# mcu_gateway.net
KiCad netlist of a schematic drawn in Altium Designer
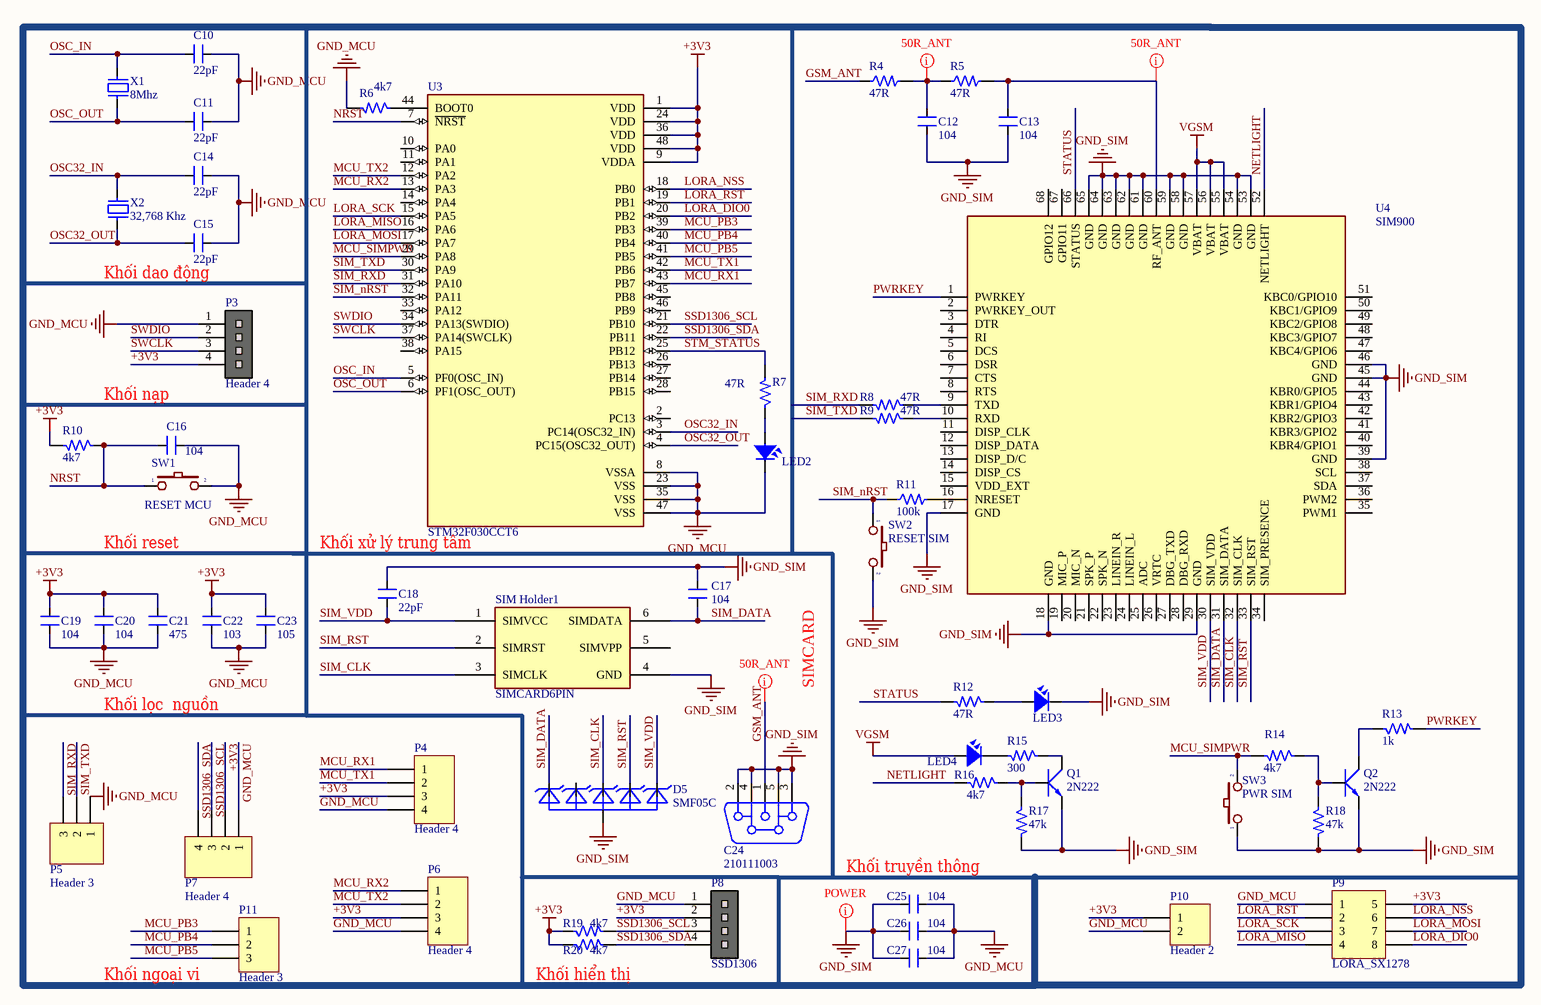
[diagram p0: mcu_gateway.SchDoc]

(export (version "E")
  (design (tool "Eeschema 10.0.6"))
  (components
    (comp (ref "C10")
      (value "22pF")
      (footprint "SM-0805")
      (description "Cap SMD")
      (libsource (lib "syhaunguyen") (part "CM"))
    )
    (comp (ref "C11")
      (value "22pF")
      (footprint "SM-0805")
      (description "Cap SMD")
      (libsource (lib "syhaunguyen") (part "CM"))
    )
    (comp (ref "C12")
      (value "104")
      (footprint "SM-0805")
      (description "Cap SMD")
      (libsource (lib "syhaunguyen") (part "CM"))
    )
    (comp (ref "C13")
      (value "104")
      (footprint "SM-0805")
      (description "Cap SMD")
      (libsource (lib "syhaunguyen") (part "CM"))
    )
    (comp (ref "C14")
      (value "22pF")
      (footprint "SM-0805")
      (description "Cap SMD")
      (libsource (lib "syhaunguyen") (part "CM"))
    )
    (comp (ref "C15")
      (value "22pF")
      (footprint "SM-0805")
      (description "Cap SMD")
      (libsource (lib "syhaunguyen") (part "CM"))
    )
    (comp (ref "C16")
      (value "104")
      (footprint "SM-0805")
      (description "Cap SMD")
      (libsource (lib "syhaunguyen") (part "CM"))
    )
    (comp (ref "C17")
      (value "104")
      (footprint "SM-0805")
      (description "Cap SMD")
      (libsource (lib "syhaunguyen") (part "CM"))
    )
    (comp (ref "C18")
      (value "22pF")
      (footprint "SM-0805")
      (description "Cap SMD")
      (libsource (lib "syhaunguyen") (part "CM"))
    )
    (comp (ref "C19")
      (value "104")
      (footprint "SM-0805")
      (description "Cap SMD")
      (libsource (lib "syhaunguyen") (part "CM"))
    )
    (comp (ref "C20")
      (value "104")
      (footprint "SM-0805")
      (description "Cap SMD")
      (libsource (lib "syhaunguyen") (part "CM"))
    )
    (comp (ref "C21")
      (value "475")
      (footprint "SM-0805")
      (description "Cap SMD")
      (libsource (lib "syhaunguyen") (part "CM"))
    )
    (comp (ref "C22")
      (value "103")
      (footprint "SM-0805")
      (description "Cap SMD")
      (libsource (lib "syhaunguyen") (part "CM"))
    )
    (comp (ref "C23")
      (value "105")
      (footprint "SM-0805")
      (description "Cap SMD")
      (libsource (lib "syhaunguyen") (part "CM"))
    )
    (comp (ref "C24")
      (value "210111003")
      (footprint "SMA-RA")
      (description "CONNECTOR ANTEN")
      (fields
        (field (name "MANUFACTURER") "Würth Elektronik eiSos GmbH")
        (field (name "CREATED BY") "Christin Zierenner")
      )
      (libsource (lib "TechMT.VN_Lib_Project v2") (part "CON Ant"))
    )
    (comp (ref "C25")
      (value "104")
      (footprint "SM-0805")
      (description "Cap SMD")
      (libsource (lib "syhaunguyen") (part "CM"))
    )
    (comp (ref "C26")
      (value "104")
      (footprint "SM-0805")
      (description "Cap SMD")
      (libsource (lib "syhaunguyen") (part "CM"))
    )
    (comp (ref "C27")
      (value "104")
      (footprint "SM-0805")
      (description "Cap SMD")
      (libsource (lib "syhaunguyen") (part "CM"))
    )
    (comp (ref "D5")
      (value "SMF05C")
      (footprint "SC70-6")
      (description "12.5V Clamp 8A _8/20Âµs_ Ipp Tvs Diode Surface Mount SC-88/SC70-6/SOT-363")
      (fields (field (name "MF") "ON Semiconductor"))
      (libsource (lib "SMF05C") (part "SMF05C"))
    )
    (comp (ref "LED2")
      (value "LED")
      (footprint "LED-0805-Green")
      (libsource (lib "TechMT.VN_Lib_Project v2") (part "LED SMD"))
    )
    (comp (ref "LED3")
      (value "LED")
      (footprint "LED-0805-Green")
      (libsource (lib "TechMT.VN_Lib_Project v2") (part "LED SMD"))
    )
    (comp (ref "LED4")
      (value "LED")
      (footprint "LED-0805-Green")
      (libsource (lib "TechMT.VN_Lib_Project v2") (part "LED SMD"))
    )
    (comp (ref "P3")
      (value "Header 4")
      (footprint "HDR 1X4")
      (description "Header, 4-Pin")
      (libsource (lib "Ayric connectors") (part "Header 4"))
    )
    (comp (ref "P4")
      (value "Header 4")
      (footprint "HDR1X4")
      (description "Header, 4-Pin")
      (fields (field (name "PUBLISHER") "Altium Limited"))
      (libsource (lib "Library AL") (part "Header 4"))
    )
    (comp (ref "P5")
      (value "Header 3")
      (footprint "HDR1X3")
      (description "Header, 3-Pin")
      (fields (field (name "PUBLISHER") "Altium Limited"))
      (libsource (lib "") (part "Header 3_1"))
    )
    (comp (ref "P6")
      (value "Header 4")
      (footprint "HDR1X4")
      (description "Header, 4-Pin")
      (fields (field (name "PUBLISHER") "Altium Limited"))
      (libsource (lib "Library AL") (part "Header 4"))
    )
    (comp (ref "P7")
      (value "Header 4")
      (footprint "HDR1X4")
      (description "Header, 4-Pin")
      (fields (field (name "PUBLISHER") "Altium Limited"))
      (libsource (lib "") (part "Header 4_1"))
    )
    (comp (ref "P8")
      (value "SSD1306")
      (footprint "HDR 1X4")
      (description "Header, 4-Pin")
      (libsource (lib "Ayric connectors") (part "Header 4"))
    )
    (comp (ref "P9")
      (value "LORA_SX1278")
      (footprint "HDR2X4_CEN")
      (description "Header, 4-Pin, Dual row")
      (fields (field (name "PUBLISHER") "Altium Limited"))
      (libsource (lib "Library AL") (part "Header 4X2A"))
    )
    (comp (ref "P10")
      (value "Header 2")
      (footprint "HDR1X2")
      (description "Header, 2-Pin")
      (fields (field (name "PUBLISHER") "Altium Limited"))
      (libsource (lib "Library AL") (part "Header 2"))
    )
    (comp (ref "P11")
      (value "Header 3")
      (footprint "HDR1X3")
      (description "Header, 3-Pin")
      (fields (field (name "PUBLISHER") "Altium Limited"))
      (libsource (lib "Library AL") (part "Header 3"))
    )
    (comp (ref "Q1")
      (value "2N222")
      (footprint "TO92-123")
      (description "NPN 600mW, ECB")
      (fields (field (name "CREAT BY") "MT-TECH.VN"))
      (libsource (lib "TechMT.VN_Lib_Project v2") (part "2N222"))
    )
    (comp (ref "Q2")
      (value "2N222")
      (footprint "TO92-123")
      (description "NPN 600mW, ECB")
      (fields (field (name "CREAT BY") "MT-TECH.VN"))
      (libsource (lib "TechMT.VN_Lib_Project v2") (part "2N222"))
    )
    (comp (ref "R4")
      (value "47R")
      (footprint "R-0805")
      (description "dien tro")
      (libsource (lib "oggy") (part "resistor"))
    )
    (comp (ref "R5")
      (value "47R")
      (footprint "R-0805")
      (description "dien tro")
      (libsource (lib "oggy") (part "resistor"))
    )
    (comp (ref "R6")
      (value "4k7")
      (footprint "R-0805")
      (description "dien tro")
      (libsource (lib "oggy") (part "resistor"))
    )
    (comp (ref "R7")
      (value "47R")
      (footprint "R-0805")
      (description "dien tro")
      (libsource (lib "oggy") (part "resistor"))
    )
    (comp (ref "R8")
      (value "47R")
      (footprint "R-0805")
      (description "dien tro")
      (libsource (lib "oggy") (part "resistor"))
    )
    (comp (ref "R9")
      (value "47R")
      (footprint "R-0805")
      (description "dien tro")
      (libsource (lib "oggy") (part "resistor"))
    )
    (comp (ref "R10")
      (value "4k7")
      (footprint "R-0805")
      (description "dien tro")
      (libsource (lib "oggy") (part "resistor"))
    )
    (comp (ref "R11")
      (value "100k")
      (footprint "R-0805")
      (description "dien tro")
      (libsource (lib "oggy") (part "resistor"))
    )
    (comp (ref "R12")
      (value "47R")
      (footprint "R-0805")
      (description "dien tro")
      (libsource (lib "oggy") (part "resistor"))
    )
    (comp (ref "R13")
      (value "1k")
      (footprint "R-0805")
      (description "dien tro")
      (libsource (lib "oggy") (part "resistor"))
    )
    (comp (ref "R14")
      (value "4k7")
      (footprint "R-0805")
      (description "dien tro")
      (libsource (lib "oggy") (part "resistor"))
    )
    (comp (ref "R15")
      (value "300")
      (footprint "R-0805")
      (description "dien tro")
      (libsource (lib "oggy") (part "resistor"))
    )
    (comp (ref "R16")
      (value "4k7")
      (footprint "R-0805")
      (description "dien tro")
      (libsource (lib "oggy") (part "resistor"))
    )
    (comp (ref "R17")
      (value "47k")
      (footprint "R-0805")
      (description "dien tro")
      (libsource (lib "oggy") (part "resistor"))
    )
    (comp (ref "R18")
      (value "47k")
      (footprint "R-0805")
      (description "dien tro")
      (libsource (lib "oggy") (part "resistor"))
    )
    (comp (ref "R19")
      (value "4k7")
      (footprint "R-0805")
      (description "dien tro")
      (libsource (lib "oggy") (part "resistor"))
    )
    (comp (ref "R20")
      (value "4k7")
      (footprint "R-0805")
      (description "dien tro")
      (libsource (lib "oggy") (part "resistor"))
    )
    (comp (ref "SIM Holder1")
      (value "SIMCARD6PIN")
      (footprint "SIMCARD6pin")
      (libsource (lib "AYRIC Library") (part "SIMCARD6PIN"))
    )
    (comp (ref "SW1")
      (value "RESET MCU")
      (footprint "SW1-SMD")
      (description "Switch button 2 pin")
      (libsource (lib "TechMT.VN_Lib_Project v2") (part "SW2"))
    )
    (comp (ref "SW2")
      (value "RESET SIM")
      (footprint "SW1-SMD")
      (description "Switch button 2 pin")
      (libsource (lib "TechMT.VN_Lib_Project v2") (part "SW2"))
    )
    (comp (ref "SW3")
      (value "PWR SIM")
      (footprint "SW1-SMD")
      (description "Switch button 2 pin")
      (libsource (lib "TechMT.VN_Lib_Project v2") (part "SW2"))
    )
    (comp (ref "U3")
      (value "STM32F030CCT6")
      (footprint "QFP50P900X900X160-48N")
      (description "ARMÂ® CortexÂ®-M0 STM32F0 Microcontroller IC 32-Bit 48MHz 256KB _256K x 8_ FLASH 48-LQFP _7x7_")
      (fields (field (name "MF") "STMicroelectronics") (field (name "DIGI-KEY_PART_NUMBER") "497-17332-2-ND"))
      (libsource (lib "STM32F030CCT6") (part "STM32F030CCT6"))
    )
    (comp (ref "U4") (value "SIM900") (footprint "SIM900") (libsource (lib "AYRIC Library") (part "SIM900")))
    (comp (ref "X1")
      (value "8Mhz")
      (footprint "XT2")
      (description "Crystal For all Crystal 2pin.")
      (libsource (lib "syhaunguyen") (part "XT2"))
    )
    (comp (ref "X2")
      (value "32,768 Khz")
      (footprint "XT32k")
      (description "Crystal 32,768kHz for timer real")
      (libsource (lib "syhaunguyen") (part "XT32k"))
    )
  )
  (nets
    (net (code "1") (name "+3V3") (class "Default")
      (node (ref "C19") (pin "2") (pinfunction "2_2") (pintype "passive"))
      (node (ref "C20") (pin "2") (pinfunction "2_2") (pintype "passive"))
      (node (ref "C21") (pin "2") (pinfunction "2_2") (pintype "passive"))
      (node (ref "C22") (pin "2") (pinfunction "2_2") (pintype "passive"))
      (node (ref "C23") (pin "2") (pinfunction "2_2") (pintype "passive"))
      (node (ref "P10") (pin "1") (pinfunction "1_1") (pintype "passive"))
      (node (ref "P3") (pin "4") (pinfunction "4_4") (pintype "passive"))
      (node (ref "P4") (pin "3") (pinfunction "3_3") (pintype "passive"))
      (node (ref "P6") (pin "3") (pinfunction "3_3") (pintype "passive"))
      (node (ref "P7") (pin "2") (pinfunction "2_2") (pintype "passive"))
      (node (ref "P8") (pin "2") (pinfunction "2_2") (pintype "passive"))
      (node (ref "P9") (pin "5") (pinfunction "5_5") (pintype "passive"))
      (node (ref "R10") (pin "2") (pinfunction "2_2") (pintype "passive"))
      (node (ref "R19") (pin "1") (pinfunction "1_1") (pintype "passive"))
      (node (ref "R20") (pin "1") (pinfunction "1_1") (pintype "passive"))
      (node (ref "U3") (pin "1") (pinfunction "VDD_1") (pintype "power_in"))
      (node (ref "U3") (pin "24") (pinfunction "VDD_24") (pintype "power_in"))
      (node (ref "U3") (pin "36") (pinfunction "VDD_36") (pintype "power_in"))
      (node (ref "U3") (pin "48") (pinfunction "VDD_48") (pintype "power_in"))
      (node (ref "U3") (pin "9") (pinfunction "VDDA_9") (pintype "power_in"))
    )
    (net (code "2") (name "/GSM_ANT") (class "Default")
      (node (ref "C24") (pin "1") (pinfunction "1_1") (pintype "passive"))
      (node (ref "R4") (pin "1") (pinfunction "1_1") (pintype "passive"))
    )
    (net (code "3") (name "/LORA_DIO0") (class "Default")
      (node (ref "P9") (pin "8") (pinfunction "8_8") (pintype "passive"))
      (node (ref "U3") (pin "20") (pinfunction "PB2_20") (pintype "bidirectional"))
    )
    (net (code "4") (name "/LORA_MISO") (class "Default")
      (node (ref "P9") (pin "4") (pinfunction "4_4") (pintype "passive"))
      (node (ref "U3") (pin "16") (pinfunction "PA6_16") (pintype "bidirectional"))
    )
    (net (code "5") (name "/LORA_MOSI") (class "Default")
      (node (ref "P9") (pin "7") (pinfunction "7_7") (pintype "passive"))
      (node (ref "U3") (pin "17") (pinfunction "PA7_17") (pintype "bidirectional"))
    )
    (net (code "6") (name "/LORA_NSS") (class "Default")
      (node (ref "P9") (pin "6") (pinfunction "6_6") (pintype "passive"))
      (node (ref "U3") (pin "18") (pinfunction "PB0_18") (pintype "bidirectional"))
    )
    (net (code "7") (name "/LORA_RST") (class "Default")
      (node (ref "P9") (pin "2") (pinfunction "2_2") (pintype "passive"))
      (node (ref "U3") (pin "19") (pinfunction "PB1_19") (pintype "bidirectional"))
    )
    (net (code "8") (name "/LORA_SCK") (class "Default")
      (node (ref "P9") (pin "3") (pinfunction "3_3") (pintype "passive"))
      (node (ref "U3") (pin "15") (pinfunction "PA5_15") (pintype "bidirectional"))
    )
    (net (code "9") (name "/MCU_PB3") (class "Default")
      (node (ref "P11") (pin "1") (pinfunction "1_1") (pintype "passive"))
      (node (ref "U3") (pin "39") (pinfunction "PB3_39") (pintype "bidirectional"))
    )
    (net (code "10") (name "/MCU_PB4") (class "Default")
      (node (ref "P11") (pin "2") (pinfunction "2_2") (pintype "passive"))
      (node (ref "U3") (pin "40") (pinfunction "PB4_40") (pintype "bidirectional"))
    )
    (net (code "11") (name "/MCU_PB5") (class "Default")
      (node (ref "P11") (pin "3") (pinfunction "3_3") (pintype "passive"))
      (node (ref "U3") (pin "41") (pinfunction "PB5_41") (pintype "bidirectional"))
    )
    (net (code "12") (name "/MCU_RX1") (class "Default")
      (node (ref "P4") (pin "1") (pinfunction "1_1") (pintype "passive"))
      (node (ref "U3") (pin "43") (pinfunction "PB7_43") (pintype "bidirectional"))
    )
    (net (code "13") (name "/MCU_RX2") (class "Default")
      (node (ref "P6") (pin "1") (pinfunction "1_1") (pintype "passive"))
      (node (ref "U3") (pin "13") (pinfunction "PA3_13") (pintype "bidirectional"))
    )
    (net (code "14") (name "/MCU_SIMPWR") (class "Default")
      (node (ref "R14") (pin "2") (pinfunction "2_2") (pintype "passive"))
      (node (ref "SW3") (pin "2") (pinfunction "2_2") (pintype "passive"))
      (node (ref "U3") (pin "29") (pinfunction "PA8_29") (pintype "bidirectional"))
    )
    (net (code "15") (name "/MCU_TX1") (class "Default")
      (node (ref "P4") (pin "2") (pinfunction "2_2") (pintype "passive"))
      (node (ref "U3") (pin "42") (pinfunction "PB6_42") (pintype "bidirectional"))
    )
    (net (code "16") (name "/MCU_TX2") (class "Default")
      (node (ref "P6") (pin "2") (pinfunction "2_2") (pintype "passive"))
      (node (ref "U3") (pin "12") (pinfunction "PA2_12") (pintype "bidirectional"))
    )
    (net (code "17") (name "/NETLIGHT") (class "Default")
      (node (ref "R16") (pin "2") (pinfunction "2_2") (pintype "passive"))
      (node (ref "U4") (pin "52") (pinfunction "NETLIGHT_52") (pintype "passive"))
    )
    (net (code "18") (name "/NRST") (class "Default")
      (node (ref "C16") (pin "1") (pinfunction "1_1") (pintype "passive"))
      (node (ref "R10") (pin "1") (pinfunction "1_1") (pintype "passive"))
      (node (ref "SW1") (pin "1") (pinfunction "1_1") (pintype "passive"))
      (node (ref "U3") (pin "7") (pinfunction "~{NRST}_7") (pintype "bidirectional"))
    )
    (net (code "19") (name "/OSC32_IN") (class "Default")
      (node (ref "C14") (pin "2") (pinfunction "2_2") (pintype "passive"))
      (node (ref "U3") (pin "3") (pinfunction "PC14(OSC32_IN)_3") (pintype "bidirectional"))
      (node (ref "X2") (pin "2") (pinfunction "2_2") (pintype "passive"))
    )
    (net (code "20") (name "/OSC32_OUT") (class "Default")
      (node (ref "C15") (pin "2") (pinfunction "2_2") (pintype "passive"))
      (node (ref "U3") (pin "4") (pinfunction "PC15(OSC32_OUT)_4") (pintype "bidirectional"))
      (node (ref "X2") (pin "1") (pinfunction "1_1") (pintype "passive"))
    )
    (net (code "21") (name "/OSC_IN") (class "Default")
      (node (ref "C10") (pin "2") (pinfunction "2_2") (pintype "passive"))
      (node (ref "U3") (pin "5") (pinfunction "PF0(OSC_IN)_5") (pintype "bidirectional"))
      (node (ref "X1") (pin "2") (pinfunction "2_2") (pintype "passive"))
    )
    (net (code "22") (name "/OSC_OUT") (class "Default")
      (node (ref "C11") (pin "2") (pinfunction "2_2") (pintype "passive"))
      (node (ref "U3") (pin "6") (pinfunction "PF1(OSC_OUT)_6") (pintype "bidirectional"))
      (node (ref "X1") (pin "1") (pinfunction "1_1") (pintype "passive"))
    )
    (net (code "23") (name "/PWRKEY") (class "Default")
      (node (ref "R13") (pin "2") (pinfunction "2_2") (pintype "passive"))
      (node (ref "U4") (pin "1") (pinfunction "PWRKEY_1") (pintype "passive"))
    )
    (net (code "24") (name "/SIM_CLK") (class "Default")
      (node (ref "D5") (pin "4") (pinfunction "C3_4") (pintype "passive"))
      (node (ref "SIM Holder1") (pin "3") (pinfunction "SIMCLK_3") (pintype "passive"))
      (node (ref "U4") (pin "32") (pinfunction "SIM_CLK_32") (pintype "passive"))
    )
    (net (code "25") (name "/SIM_DATA") (class "Default")
      (node (ref "C17") (pin "1") (pinfunction "1_1") (pintype "passive"))
      (node (ref "D5") (pin "1") (pinfunction "C1_1") (pintype "passive"))
      (node (ref "SIM Holder1") (pin "6") (pinfunction "SIMDATA_6") (pintype "passive"))
      (node (ref "U4") (pin "31") (pinfunction "SIM_DATA_31") (pintype "passive"))
    )
    (net (code "26") (name "/SIM_RST") (class "Default")
      (node (ref "D5") (pin "5") (pinfunction "C4_5") (pintype "passive"))
      (node (ref "SIM Holder1") (pin "2") (pinfunction "SIMRST_2") (pintype "passive"))
      (node (ref "U4") (pin "33") (pinfunction "SIM_RST_33") (pintype "passive"))
    )
    (net (code "27") (name "/SIM_RXD") (class "Default")
      (node (ref "P5") (pin "3") (pinfunction "3_3") (pintype "passive"))
      (node (ref "R8") (pin "2") (pinfunction "2_2") (pintype "passive"))
      (node (ref "U3") (pin "31") (pinfunction "PA10_31") (pintype "bidirectional"))
    )
    (net (code "28") (name "/SIM_TXD") (class "Default")
      (node (ref "P5") (pin "2") (pinfunction "2_2") (pintype "passive"))
      (node (ref "R9") (pin "2") (pinfunction "2_2") (pintype "passive"))
      (node (ref "U3") (pin "30") (pinfunction "PA9_30") (pintype "bidirectional"))
    )
    (net (code "29") (name "/SIM_VDD") (class "Default")
      (node (ref "C18") (pin "1") (pinfunction "1_1") (pintype "passive"))
      (node (ref "D5") (pin "6") (pinfunction "C5_6") (pintype "passive"))
      (node (ref "SIM Holder1") (pin "1") (pinfunction "SIMVCC_1") (pintype "passive"))
      (node (ref "U4") (pin "30") (pinfunction "SIM_VDD_30") (pintype "passive"))
    )
    (net (code "30") (name "/SIM_nRST") (class "Default")
      (node (ref "R11") (pin "1") (pinfunction "1_1") (pintype "passive"))
      (node (ref "SW2") (pin "1") (pinfunction "1_1") (pintype "passive"))
      (node (ref "U3") (pin "32") (pinfunction "PA11_32") (pintype "bidirectional"))
    )
    (net (code "31") (name "/SSD1306_SCL") (class "Default")
      (node (ref "P7") (pin "3") (pinfunction "3_3") (pintype "passive"))
      (node (ref "P8") (pin "3") (pinfunction "3_3") (pintype "passive"))
      (node (ref "R19") (pin "2") (pinfunction "2_2") (pintype "passive"))
      (node (ref "U3") (pin "21") (pinfunction "PB10_21") (pintype "bidirectional"))
    )
    (net (code "32") (name "/SSD1306_SDA") (class "Default")
      (node (ref "P7") (pin "4") (pinfunction "4_4") (pintype "passive"))
      (node (ref "P8") (pin "4") (pinfunction "4_4") (pintype "passive"))
      (node (ref "R20") (pin "2") (pinfunction "2_2") (pintype "passive"))
      (node (ref "U3") (pin "22") (pinfunction "PB11_22") (pintype "bidirectional"))
    )
    (net (code "33") (name "/STATUS") (class "Default")
      (node (ref "R12") (pin "2") (pinfunction "2_2") (pintype "passive"))
      (node (ref "U4") (pin "66") (pinfunction "STATUS_66") (pintype "passive"))
    )
    (net (code "34") (name "/STM_STATUS") (class "Default")
      (node (ref "R7") (pin "2") (pinfunction "2_2") (pintype "passive"))
      (node (ref "U3") (pin "25") (pinfunction "PB12_25") (pintype "bidirectional"))
    )
    (net (code "35") (name "/SWCLK") (class "Default")
      (node (ref "P3") (pin "3") (pinfunction "3_3") (pintype "passive"))
      (node (ref "U3") (pin "37") (pinfunction "PA14(SWCLK)_37") (pintype "bidirectional"))
    )
    (net (code "36") (name "/SWDIO") (class "Default")
      (node (ref "P3") (pin "2") (pinfunction "2_2") (pintype "passive"))
      (node (ref "U3") (pin "34") (pinfunction "PA13(SWDIO)_34") (pintype "bidirectional"))
    )
    (net (code "37") (name "GND_MCU") (class "Default")
      (node (ref "C10") (pin "1") (pinfunction "1_1") (pintype "passive"))
      (node (ref "C11") (pin "1") (pinfunction "1_1") (pintype "passive"))
      (node (ref "C14") (pin "1") (pinfunction "1_1") (pintype "passive"))
      (node (ref "C15") (pin "1") (pinfunction "1_1") (pintype "passive"))
      (node (ref "C16") (pin "2") (pinfunction "2_2") (pintype "passive"))
      (node (ref "C19") (pin "1") (pinfunction "1_1") (pintype "passive"))
      (node (ref "C20") (pin "1") (pinfunction "1_1") (pintype "passive"))
      (node (ref "C21") (pin "1") (pinfunction "1_1") (pintype "passive"))
      (node (ref "C22") (pin "1") (pinfunction "1_1") (pintype "passive"))
      (node (ref "C23") (pin "1") (pinfunction "1_1") (pintype "passive"))
      (node (ref "C25") (pin "2") (pinfunction "2_2") (pintype "passive"))
      (node (ref "C26") (pin "2") (pinfunction "2_2") (pintype "passive"))
      (node (ref "C27") (pin "2") (pinfunction "2_2") (pintype "passive"))
      (node (ref "LED2") (pin "2") (pinfunction "2_2") (pintype "passive"))
      (node (ref "P10") (pin "2") (pinfunction "2_2") (pintype "passive"))
      (node (ref "P3") (pin "1") (pinfunction "1_1") (pintype "passive"))
      (node (ref "P4") (pin "4") (pinfunction "4_4") (pintype "passive"))
      (node (ref "P5") (pin "1") (pinfunction "1_1") (pintype "passive"))
      (node (ref "P6") (pin "4") (pinfunction "4_4") (pintype "passive"))
      (node (ref "P7") (pin "1") (pinfunction "1_1") (pintype "passive"))
      (node (ref "P8") (pin "1") (pinfunction "1_1") (pintype "passive"))
      (node (ref "P9") (pin "1") (pinfunction "1_1") (pintype "passive"))
      (node (ref "R6") (pin "2") (pinfunction "2_2") (pintype "passive"))
      (node (ref "SW1") (pin "2") (pinfunction "2_2") (pintype "passive"))
      (node (ref "U3") (pin "23") (pinfunction "VSS_23") (pintype "power_in"))
      (node (ref "U3") (pin "35") (pinfunction "VSS_35") (pintype "power_in"))
      (node (ref "U3") (pin "47") (pinfunction "VSS_47") (pintype "power_in"))
      (node (ref "U3") (pin "8") (pinfunction "VSSA_8") (pintype "power_in"))
    )
    (net (code "38") (name "GND_SIM") (class "Default")
      (node (ref "C12") (pin "1") (pinfunction "1_1") (pintype "passive"))
      (node (ref "C13") (pin "1") (pinfunction "1_1") (pintype "passive"))
      (node (ref "C17") (pin "2") (pinfunction "2_2") (pintype "passive"))
      (node (ref "C18") (pin "2") (pinfunction "2_2") (pintype "passive"))
      (node (ref "C24") (pin "2") (pinfunction "2_2") (pintype "passive"))
      (node (ref "C24") (pin "3") (pinfunction "3_3") (pintype "passive"))
      (node (ref "C24") (pin "4") (pinfunction "4_4") (pintype "passive"))
      (node (ref "C24") (pin "5") (pinfunction "5_5") (pintype "passive"))
      (node (ref "C25") (pin "1") (pinfunction "1_1") (pintype "passive"))
      (node (ref "C26") (pin "1") (pinfunction "1_1") (pintype "passive"))
      (node (ref "C27") (pin "1") (pinfunction "1_1") (pintype "passive"))
      (node (ref "D5") (pin "2") (pinfunction "A_2") (pintype "passive"))
      (node (ref "LED3") (pin "2") (pinfunction "2_2") (pintype "passive"))
      (node (ref "Q1") (pin "1") (pinfunction "E_1") (pintype "passive"))
      (node (ref "Q2") (pin "1") (pinfunction "E_1") (pintype "passive"))
      (node (ref "R17") (pin "2") (pinfunction "2_2") (pintype "passive"))
      (node (ref "R18") (pin "2") (pinfunction "2_2") (pintype "passive"))
      (node (ref "SIM Holder1") (pin "4") (pinfunction "GND_4") (pintype "passive"))
      (node (ref "SW2") (pin "2") (pinfunction "2_2") (pintype "passive"))
      (node (ref "SW3") (pin "1") (pinfunction "1_1") (pintype "passive"))
      (node (ref "U4") (pin "17") (pinfunction "GND_17") (pintype "passive"))
      (node (ref "U4") (pin "18") (pinfunction "GND_18") (pintype "passive"))
      (node (ref "U4") (pin "29") (pinfunction "GND_29") (pintype "passive"))
      (node (ref "U4") (pin "39") (pinfunction "GND_39") (pintype "passive"))
      (node (ref "U4") (pin "45") (pinfunction "GND_45") (pintype "passive"))
      (node (ref "U4") (pin "46") (pinfunction "GND_46") (pintype "passive"))
      (node (ref "U4") (pin "53") (pinfunction "GND_53") (pintype "passive"))
      (node (ref "U4") (pin "54") (pinfunction "GND_54") (pintype "passive"))
      (node (ref "U4") (pin "58") (pinfunction "GND_58") (pintype "passive"))
      (node (ref "U4") (pin "59") (pinfunction "GND_59") (pintype "passive"))
      (node (ref "U4") (pin "61") (pinfunction "GND_61") (pintype "passive"))
      (node (ref "U4") (pin "62") (pinfunction "GND_62") (pintype "passive"))
      (node (ref "U4") (pin "63") (pinfunction "GND_63") (pintype "passive"))
      (node (ref "U4") (pin "64") (pinfunction "GND_64") (pintype "passive"))
      (node (ref "U4") (pin "65") (pinfunction "GND_65") (pintype "passive"))
    )
    (net (code "39") (name "Net-(C12-Pad2)") (class "Default")
      (node (ref "C12") (pin "2") (pinfunction "2_2") (pintype "passive"))
      (node (ref "R4") (pin "2") (pinfunction "2_2") (pintype "passive"))
      (node (ref "R5") (pin "1") (pinfunction "1_1") (pintype "passive"))
    )
    (net (code "40") (name "Net-(LED2-Pad1)") (class "Default")
      (node (ref "LED2") (pin "1") (pinfunction "1_1") (pintype "passive"))
      (node (ref "R7") (pin "1") (pinfunction "1_1") (pintype "passive"))
    )
    (net (code "41") (name "Net-(LED3-Pad1)") (class "Default")
      (node (ref "LED3") (pin "1") (pinfunction "1_1") (pintype "passive"))
      (node (ref "R12") (pin "1") (pinfunction "1_1") (pintype "passive"))
    )
    (net (code "42") (name "Net-(LED4-Pad2)") (class "Default")
      (node (ref "LED4") (pin "2") (pinfunction "2_2") (pintype "passive"))
      (node (ref "R15") (pin "2") (pinfunction "2_2") (pintype "passive"))
    )
    (net (code "43") (name "Net-(Q1-B)") (class "Default")
      (node (ref "Q1") (pin "2") (pinfunction "B_2") (pintype "passive"))
      (node (ref "R16") (pin "1") (pinfunction "1_1") (pintype "passive"))
      (node (ref "R17") (pin "1") (pinfunction "1_1") (pintype "passive"))
    )
    (net (code "44") (name "Net-(Q1-C)") (class "Default")
      (node (ref "Q1") (pin "3") (pinfunction "C_3") (pintype "passive"))
      (node (ref "R15") (pin "1") (pinfunction "1_1") (pintype "passive"))
    )
    (net (code "45") (name "Net-(Q2-B)") (class "Default")
      (node (ref "Q2") (pin "2") (pinfunction "B_2") (pintype "passive"))
      (node (ref "R14") (pin "1") (pinfunction "1_1") (pintype "passive"))
      (node (ref "R18") (pin "1") (pinfunction "1_1") (pintype "passive"))
    )
    (net (code "46") (name "Net-(Q2-C)") (class "Default")
      (node (ref "Q2") (pin "3") (pinfunction "C_3") (pintype "passive"))
      (node (ref "R13") (pin "1") (pinfunction "1_1") (pintype "passive"))
    )
    (net (code "47") (name "Net-(U3-BOOT0)") (class "Default")
      (node (ref "R6") (pin "1") (pinfunction "1_1") (pintype "passive"))
      (node (ref "U3") (pin "44") (pinfunction "BOOT0_44") (pintype "passive"))
    )
    (net (code "48") (name "Net-(U4-NRESET)") (class "Default")
      (node (ref "R11") (pin "2") (pinfunction "2_2") (pintype "passive"))
      (node (ref "U4") (pin "16") (pinfunction "NRESET_16") (pintype "passive"))
    )
    (net (code "49") (name "Net-(U4-RF_ANT)") (class "Default")
      (node (ref "C13") (pin "2") (pinfunction "2_2") (pintype "passive"))
      (node (ref "R5") (pin "2") (pinfunction "2_2") (pintype "passive"))
      (node (ref "U4") (pin "60") (pinfunction "RF_ANT_60") (pintype "passive"))
    )
    (net (code "50") (name "Net-(U4-RXD)") (class "Default")
      (node (ref "R9") (pin "1") (pinfunction "1_1") (pintype "passive"))
      (node (ref "U4") (pin "10") (pinfunction "RXD_10") (pintype "passive"))
    )
    (net (code "51") (name "Net-(U4-TXD)") (class "Default")
      (node (ref "R8") (pin "1") (pinfunction "1_1") (pintype "passive"))
      (node (ref "U4") (pin "9") (pinfunction "TXD_9") (pintype "passive"))
    )
    (net (code "52") (name "VGSM") (class "Default")
      (node (ref "LED4") (pin "1") (pinfunction "1_1") (pintype "passive"))
      (node (ref "U4") (pin "55") (pinfunction "VBAT_55") (pintype "passive"))
      (node (ref "U4") (pin "56") (pinfunction "VBAT_56") (pintype "passive"))
      (node (ref "U4") (pin "57") (pinfunction "VBAT_57") (pintype "passive"))
    )
    (net (code "53") (name "unconnected-(D5-C2-Pad3)") (class "Default")
      (node (ref "D5") (pin "3") (pinfunction "C2_3") (pintype "passive"))
    )
    (net (code "54") (name "unconnected-(SIM Holder1-SIMVPP-Pad5)") (class "Default")
      (node (ref "SIM Holder1") (pin "5") (pinfunction "SIMVPP_5") (pintype "passive"))
    )
    (net (code "55") (name "unconnected-(U3-PA0-Pad10)") (class "Default")
      (node (ref "U3") (pin "10") (pinfunction "PA0_10") (pintype "bidirectional"))
    )
    (net (code "56") (name "unconnected-(U3-PA1-Pad11)") (class "Default")
      (node (ref "U3") (pin "11") (pinfunction "PA1_11") (pintype "bidirectional"))
    )
    (net (code "57") (name "unconnected-(U3-PA4-Pad14)") (class "Default")
      (node (ref "U3") (pin "14") (pinfunction "PA4_14") (pintype "bidirectional"))
    )
    (net (code "58") (name "unconnected-(U3-PA12-Pad33)") (class "Default")
      (node (ref "U3") (pin "33") (pinfunction "PA12_33") (pintype "bidirectional"))
    )
    (net (code "59") (name "unconnected-(U3-PA15-Pad38)") (class "Default")
      (node (ref "U3") (pin "38") (pinfunction "PA15_38") (pintype "bidirectional"))
    )
    (net (code "60") (name "unconnected-(U3-PB8-Pad45)") (class "Default")
      (node (ref "U3") (pin "45") (pinfunction "PB8_45") (pintype "bidirectional"))
    )
    (net (code "61") (name "unconnected-(U3-PB9-Pad46)") (class "Default")
      (node (ref "U3") (pin "46") (pinfunction "PB9_46") (pintype "bidirectional"))
    )
    (net (code "62") (name "unconnected-(U3-PB13-Pad26)") (class "Default")
      (node (ref "U3") (pin "26") (pinfunction "PB13_26") (pintype "bidirectional"))
    )
    (net (code "63") (name "unconnected-(U3-PB14-Pad27)") (class "Default")
      (node (ref "U3") (pin "27") (pinfunction "PB14_27") (pintype "bidirectional"))
    )
    (net (code "64") (name "unconnected-(U3-PB15-Pad28)") (class "Default")
      (node (ref "U3") (pin "28") (pinfunction "PB15_28") (pintype "bidirectional"))
    )
    (net (code "65") (name "unconnected-(U3-PC13-Pad2)") (class "Default")
      (node (ref "U3") (pin "2") (pinfunction "PC13_2") (pintype "bidirectional"))
    )
    (net (code "66") (name "unconnected-(U4-ADC-Pad25)") (class "Default")
      (node (ref "U4") (pin "25") (pinfunction "ADC_25") (pintype "passive"))
    )
    (net (code "67") (name "unconnected-(U4-CTS-Pad7)") (class "Default")
      (node (ref "U4") (pin "7") (pinfunction "CTS_7") (pintype "passive"))
    )
    (net (code "68") (name "unconnected-(U4-DBG_RXD-Pad28)") (class "Default")
      (node (ref "U4") (pin "28") (pinfunction "DBG_RXD_28") (pintype "passive"))
    )
    (net (code "69") (name "unconnected-(U4-DBG_TXD-Pad27)") (class "Default")
      (node (ref "U4") (pin "27") (pinfunction "DBG_TXD_27") (pintype "passive"))
    )
    (net (code "70") (name "unconnected-(U4-DCS-Pad5)") (class "Default")
      (node (ref "U4") (pin "5") (pinfunction "DCS_5") (pintype "passive"))
    )
    (net (code "71") (name "unconnected-(U4-DISP_CLK-Pad11)") (class "Default")
      (node (ref "U4") (pin "11") (pinfunction "DISP_CLK_11") (pintype "passive"))
    )
    (net (code "72") (name "unconnected-(U4-DISP_CS-Pad14)") (class "Default")
      (node (ref "U4") (pin "14") (pinfunction "DISP_CS_14") (pintype "passive"))
    )
    (net (code "73") (name "unconnected-(U4-DISP_DATA-Pad12)") (class "Default")
      (node (ref "U4") (pin "12") (pinfunction "DISP_DATA_12") (pintype "passive"))
    )
    (net (code "74") (name "unconnected-(U4-DISP_D{slash}C-Pad13)") (class "Default")
      (node (ref "U4") (pin "13") (pinfunction "DISP_D/C_13") (pintype "passive"))
    )
    (net (code "75") (name "unconnected-(U4-DSR-Pad6)") (class "Default")
      (node (ref "U4") (pin "6") (pinfunction "DSR_6") (pintype "passive"))
    )
    (net (code "76") (name "unconnected-(U4-DTR-Pad3)") (class "Default")
      (node (ref "U4") (pin "3") (pinfunction "DTR_3") (pintype "passive"))
    )
    (net (code "77") (name "unconnected-(U4-GPIO11-Pad67)") (class "Default")
      (node (ref "U4") (pin "67") (pinfunction "GPIO11_67") (pintype "passive"))
    )
    (net (code "78") (name "unconnected-(U4-GPIO12-Pad68)") (class "Default")
      (node (ref "U4") (pin "68") (pinfunction "GPIO12_68") (pintype "passive"))
    )
    (net (code "79") (name "unconnected-(U4-KBC0{slash}GPIO10-Pad51)") (class "Default")
      (node (ref "U4") (pin "51") (pinfunction "KBC0/GPIO10_51") (pintype "passive"))
    )
    (net (code "80") (name "unconnected-(U4-KBC1{slash}GPIO9-Pad50)") (class "Default")
      (node (ref "U4") (pin "50") (pinfunction "KBC1/GPIO9_50") (pintype "passive"))
    )
    (net (code "81") (name "unconnected-(U4-KBC2{slash}GPIO8-Pad49)") (class "Default")
      (node (ref "U4") (pin "49") (pinfunction "KBC2/GPIO8_49") (pintype "passive"))
    )
    (net (code "82") (name "unconnected-(U4-KBC3{slash}GPIO7-Pad48)") (class "Default")
      (node (ref "U4") (pin "48") (pinfunction "KBC3/GPIO7_48") (pintype "passive"))
    )
    (net (code "83") (name "unconnected-(U4-KBC4{slash}GPIO6-Pad47)") (class "Default")
      (node (ref "U4") (pin "47") (pinfunction "KBC4/GPIO6_47") (pintype "passive"))
    )
    (net (code "84") (name "unconnected-(U4-KBR0{slash}GPIO5-Pad44)") (class "Default")
      (node (ref "U4") (pin "44") (pinfunction "KBR0/GPIO5_44") (pintype "passive"))
    )
    (net (code "85") (name "unconnected-(U4-KBR1{slash}GPIO4-Pad43)") (class "Default")
      (node (ref "U4") (pin "43") (pinfunction "KBR1/GPIO4_43") (pintype "passive"))
    )
    (net (code "86") (name "unconnected-(U4-KBR2{slash}GPIO3-Pad42)") (class "Default")
      (node (ref "U4") (pin "42") (pinfunction "KBR2/GPIO3_42") (pintype "passive"))
    )
    (net (code "87") (name "unconnected-(U4-KBR3{slash}GPIO2-Pad41)") (class "Default")
      (node (ref "U4") (pin "41") (pinfunction "KBR3/GPIO2_41") (pintype "passive"))
    )
    (net (code "88") (name "unconnected-(U4-KBR4{slash}GPIO1-Pad40)") (class "Default")
      (node (ref "U4") (pin "40") (pinfunction "KBR4/GPIO1_40") (pintype "passive"))
    )
    (net (code "89") (name "unconnected-(U4-LINEIN_L-Pad24)") (class "Default")
      (node (ref "U4") (pin "24") (pinfunction "LINEIN_L_24") (pintype "passive"))
    )
    (net (code "90") (name "unconnected-(U4-LINEIN_R-Pad23)") (class "Default")
      (node (ref "U4") (pin "23") (pinfunction "LINEIN_R_23") (pintype "passive"))
    )
    (net (code "91") (name "unconnected-(U4-MIC_N-Pad20)") (class "Default")
      (node (ref "U4") (pin "20") (pinfunction "MIC_N_20") (pintype "passive"))
    )
    (net (code "92") (name "unconnected-(U4-MIC_P-Pad19)") (class "Default")
      (node (ref "U4") (pin "19") (pinfunction "MIC_P_19") (pintype "passive"))
    )
    (net (code "93") (name "unconnected-(U4-PWM1-Pad35)") (class "Default")
      (node (ref "U4") (pin "35") (pinfunction "PWM1_35") (pintype "passive"))
    )
    (net (code "94") (name "unconnected-(U4-PWM2-Pad36)") (class "Default")
      (node (ref "U4") (pin "36") (pinfunction "PWM2_36") (pintype "passive"))
    )
    (net (code "95") (name "unconnected-(U4-PWRKEY_OUT-Pad2)") (class "Default")
      (node (ref "U4") (pin "2") (pinfunction "PWRKEY_OUT_2") (pintype "passive"))
    )
    (net (code "96") (name "unconnected-(U4-RI-Pad4)") (class "Default")
      (node (ref "U4") (pin "4") (pinfunction "RI_4") (pintype "passive"))
    )
    (net (code "97") (name "unconnected-(U4-RTS-Pad8)") (class "Default")
      (node (ref "U4") (pin "8") (pinfunction "RTS_8") (pintype "passive"))
    )
    (net (code "98") (name "unconnected-(U4-SCL-Pad38)") (class "Default")
      (node (ref "U4") (pin "38") (pinfunction "SCL_38") (pintype "passive"))
    )
    (net (code "99") (name "unconnected-(U4-SDA-Pad37)") (class "Default")
      (node (ref "U4") (pin "37") (pinfunction "SDA_37") (pintype "passive"))
    )
    (net (code "100") (name "unconnected-(U4-SIM_PRESENCE-Pad34)") (class "Default")
      (node (ref "U4") (pin "34") (pinfunction "SIM_PRESENCE_34") (pintype "passive"))
    )
    (net (code "101") (name "unconnected-(U4-SPK_N-Pad22)") (class "Default")
      (node (ref "U4") (pin "22") (pinfunction "SPK_N_22") (pintype "passive"))
    )
    (net (code "102") (name "unconnected-(U4-SPK_P-Pad21)") (class "Default")
      (node (ref "U4") (pin "21") (pinfunction "SPK_P_21") (pintype "passive"))
    )
    (net (code "103") (name "unconnected-(U4-VDD_EXT-Pad15)") (class "Default")
      (node (ref "U4") (pin "15") (pinfunction "VDD_EXT_15") (pintype "passive"))
    )
    (net (code "104") (name "unconnected-(U4-VRTC-Pad26)") (class "Default")
      (node (ref "U4") (pin "26") (pinfunction "VRTC_26") (pintype "passive"))
    )
  )
)
